# 3_Demo_PCB.net
KiCad netlist of a schematic drawn in Altium Designer
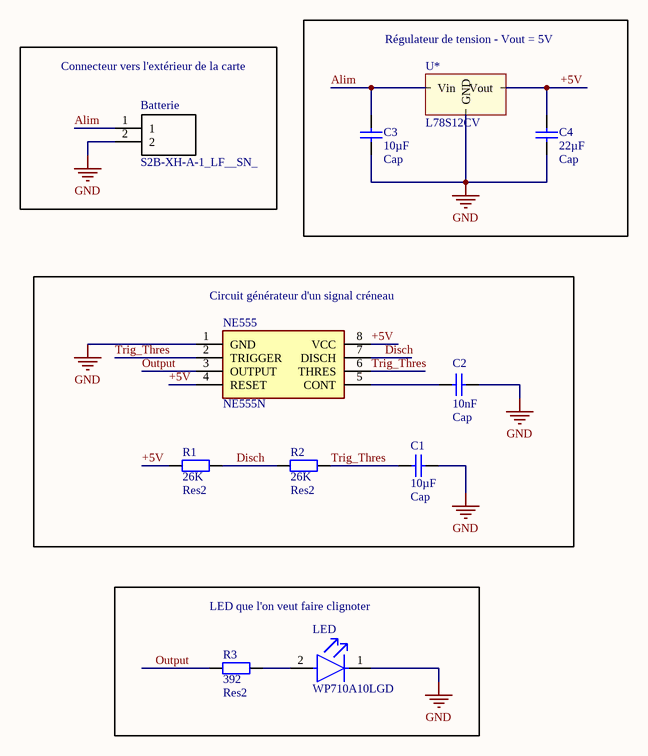
[diagram p0: 3_Demo_PCB.SchDoc]

(export (version "E")
  (design (tool "Eeschema 10.0.6"))
  (components
    (comp (ref "Batterie")
      (value "S2B-XH-A-1_LF__SN_")
      (footprint "S2B-XH-A")
      (description "Connector")
      (fields (field (name "MANUFACTURER_PART_NUMBER") "S2B-XH-A-1(LF)(SN)"))
      (libsource (lib "SamacSys") (part "S2B-XH-A-1_LF__SN_"))
    )
    (comp (ref "C1")
      (value "Cap")
      (footprint "Capacitor 1206")
      (description "Capacitor")
      (fields (field (name "ALTIUM_VALUE") "10µF") (field (name "PUBLISHER") "Altium Limited"))
      (libsource (lib "Miscellaneous Devices") (part "Cap"))
    )
    (comp (ref "C2")
      (value "Cap")
      (footprint "Capacitor 1206")
      (description "Capacitor")
      (fields (field (name "ALTIUM_VALUE") "10nF") (field (name "PUBLISHER") "Altium Limited"))
      (libsource (lib "Miscellaneous Devices") (part "Cap"))
    )
    (comp (ref "C3")
      (value "Cap")
      (footprint "Capacitor 1206")
      (description "Capacitor")
      (fields (field (name "ALTIUM_VALUE") "10µF") (field (name "PUBLISHER") "Altium Limited"))
      (libsource (lib "Miscellaneous Devices") (part "Cap"))
    )
    (comp (ref "C4")
      (value "Cap")
      (footprint "Capacitor 1206")
      (description "Capacitor")
      (fields (field (name "ALTIUM_VALUE") "22µF") (field (name "PUBLISHER") "Altium Limited"))
      (libsource (lib "Miscellaneous Devices") (part "Cap"))
    )
    (comp (ref "LED")
      (value "WP710A10LGD")
      (footprint "FP-WP710A10LGD-MFG")
      (description "WP710A10LGD LED Thru-Hole PCB Green T-1 3mm Green Lens 2 mA 568 nm 2 mcd Round")
      (libsource (lib "Altium Content Vault") (part "8706943c75ba83719d021d2fdc84c58"))
    )
    (comp (ref "NE555")
      (value "NE555N")
      (footprint "SamacSys:DIP762W56P254L959H533Q8N")
      (description "Integrated Circuit")
      (libsource (lib "Robot_2020") (part "NE555N"))
    )
    (comp (ref "R1")
      (value "Res2")
      (footprint "Resistor 1206")
      (description "Resistor")
      (fields (field (name "ALTIUM_VALUE") "26K") (field (name "PUBLISHER") "Altium Limited"))
      (libsource (lib "Miscellaneous Devices") (part "Res2"))
    )
    (comp (ref "R2")
      (value "Res2")
      (footprint "Resistor 1206")
      (description "Resistor")
      (fields (field (name "ALTIUM_VALUE") "26K") (field (name "PUBLISHER") "Altium Limited"))
      (libsource (lib "Miscellaneous Devices") (part "Res2"))
    )
    (comp (ref "R3")
      (value "Res2")
      (footprint "Resistor 1206")
      (description "Resistor")
      (fields (field (name "ALTIUM_VALUE") "392") (field (name "PUBLISHER") "Altium Limited"))
      (libsource (lib "Miscellaneous Devices") (part "Res2"))
    )
    (comp (ref "U*")
      (value "L78S12CV")
      (footprint "R-78B")
      (libsource (lib "Robot_2020") (part "Régulateur de tension linéaire"))
    )
  )
  (nets
    (net (code "1") (name "/+5V") (class "Default")
      (node (ref "C4") (pin "2") (pinfunction "2_2") (pintype "passive"))
      (node (ref "NE555") (pin "4") (pinfunction "RESET_4") (pintype "passive"))
      (node (ref "NE555") (pin "8") (pinfunction "VCC_8") (pintype "passive"))
      (node (ref "R1") (pin "2") (pinfunction "2_2") (pintype "passive"))
      (node (ref "U*") (pin "1") (pinfunction "Vout_1") (pintype "passive"))
    )
    (net (code "2") (name "/Alim") (class "Default")
      (node (ref "Batterie") (pin "1") (pinfunction "1_1") (pintype "passive"))
      (node (ref "C3") (pin "1") (pinfunction "1_1") (pintype "passive"))
      (node (ref "U*") (pin "3") (pinfunction "Vin_3") (pintype "passive"))
    )
    (net (code "3") (name "/Disch") (class "Default")
      (node (ref "NE555") (pin "7") (pinfunction "DISCH_7") (pintype "passive"))
      (node (ref "R1") (pin "1") (pinfunction "1_1") (pintype "passive"))
      (node (ref "R2") (pin "2") (pinfunction "2_2") (pintype "passive"))
    )
    (net (code "4") (name "/Output") (class "Default")
      (node (ref "NE555") (pin "3") (pinfunction "OUTPUT_3") (pintype "passive"))
      (node (ref "R3") (pin "2") (pinfunction "2_2") (pintype "passive"))
    )
    (net (code "5") (name "/Trig_Thres") (class "Default")
      (node (ref "C1") (pin "2") (pinfunction "2_2") (pintype "passive"))
      (node (ref "NE555") (pin "2") (pinfunction "TRIGGER_2") (pintype "passive"))
      (node (ref "NE555") (pin "6") (pinfunction "THRES_6") (pintype "passive"))
      (node (ref "R2") (pin "1") (pinfunction "1_1") (pintype "passive"))
    )
    (net (code "6") (name "GND") (class "Default")
      (node (ref "Batterie") (pin "2") (pinfunction "2_2") (pintype "passive"))
      (node (ref "C1") (pin "1") (pinfunction "1_1") (pintype "passive"))
      (node (ref "C2") (pin "2") (pinfunction "2_2") (pintype "passive"))
      (node (ref "C3") (pin "2") (pinfunction "2_2") (pintype "passive"))
      (node (ref "C4") (pin "1") (pinfunction "1_1") (pintype "passive"))
      (node (ref "LED") (pin "1") (pinfunction "C_1") (pintype "passive"))
      (node (ref "NE555") (pin "1") (pinfunction "GND_1") (pintype "passive"))
      (node (ref "U*") (pin "2") (pinfunction "GND_2") (pintype "passive"))
    )
    (net (code "7") (name "Net-(LED-A)") (class "Default")
      (node (ref "LED") (pin "2") (pinfunction "A_2") (pintype "passive"))
      (node (ref "R3") (pin "1") (pinfunction "1_1") (pintype "passive"))
    )
    (net (code "8") (name "Net-(NE555-CONT)") (class "Default")
      (node (ref "C2") (pin "1") (pinfunction "1_1") (pintype "passive"))
      (node (ref "NE555") (pin "5") (pinfunction "CONT_5") (pintype "passive"))
    )
  )
)
